# Thermostat_EEM_Cryo.net
KiCad netlist of a schematic drawn in Altium Designer
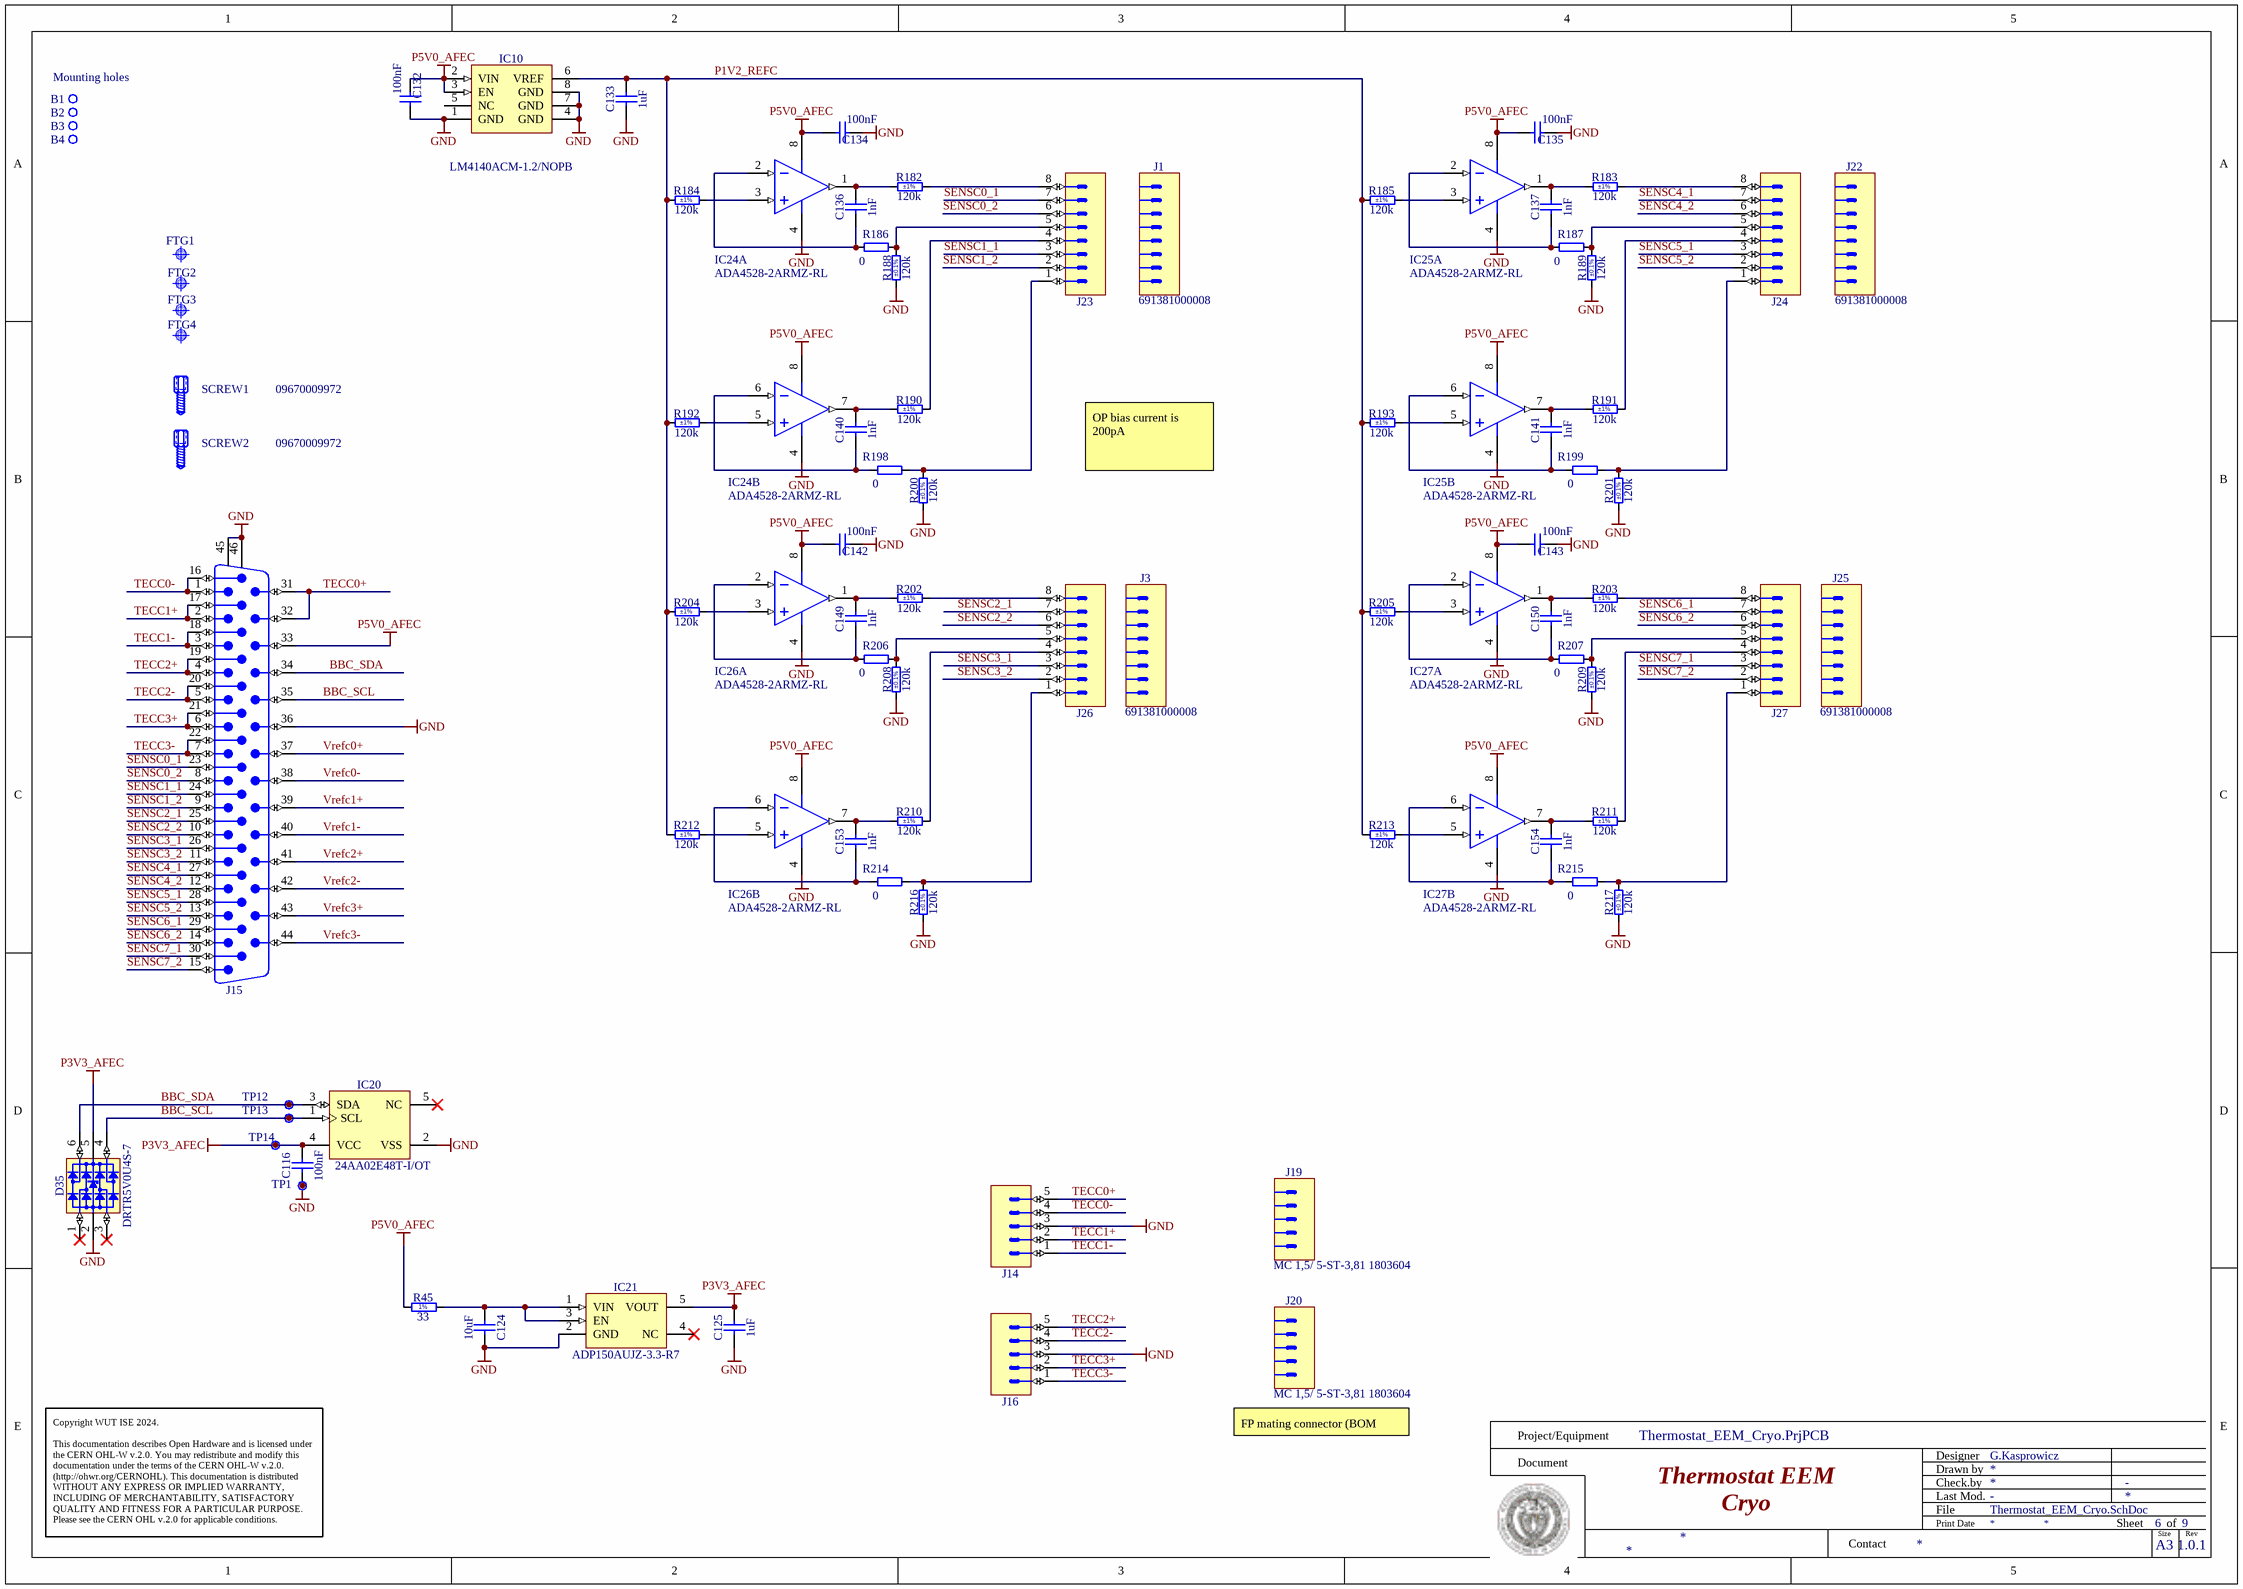
[diagram p0: Thermostat_EEM_Cryo.SchDoc]

(export (version "E")
  (design (tool "Eeschema 10.0.6"))
  (components
    (comp (ref "B1")
      (value "Plated Hole")
      (footprint "MTG320_550")
      (description "Single Terminal Socket")
      (fields (field (name "PART NUMBER") "PLATED_HOLE3.2_PAD5.5") (field (name "AUTHOR") "CERN DEM JMW"))
      (libsource (lib "Eletro-mechanical") (part "Single Terminal Socket"))
    )
    (comp (ref "B2")
      (value "Plated Hole")
      (footprint "MTG320_550")
      (description "Single Terminal Socket")
      (fields (field (name "PART NUMBER") "PLATED_HOLE3.2_PAD5.5") (field (name "AUTHOR") "CERN DEM JMW"))
      (libsource (lib "Eletro-mechanical") (part "Single Terminal Socket"))
    )
    (comp (ref "B3")
      (value "Plated Hole")
      (footprint "MTG320_550")
      (description "Single Terminal Socket")
      (fields (field (name "PART NUMBER") "PLATED_HOLE3.2_PAD5.5") (field (name "AUTHOR") "CERN DEM JMW"))
      (libsource (lib "Eletro-mechanical") (part "Single Terminal Socket"))
    )
    (comp (ref "B4")
      (value "Plated Hole")
      (footprint "MTG320_550")
      (description "Single Terminal Socket")
      (fields (field (name "PART NUMBER") "PLATED_HOLE3.2_PAD5.5") (field (name "AUTHOR") "CERN DEM JMW"))
      (libsource (lib "Eletro-mechanical") (part "Single Terminal Socket"))
    )
    (comp (ref "C116")
      (value "100nF")
      (footprint "CAPC1005X55N")
      (description "Non-polarised capacitor")
      (fields
        (field (name "PART NUMBER") "CC0402_100NF_16V_10%_X5R")
        (field (name "VOLTAGE") "16V")
        (field (name "AUTHOR") "CERN DEM JLC")
      )
      (libsource (lib "Capacitors") (part "Capacitor - non polarized"))
    )
    (comp (ref "C124")
      (value "10uF")
      (footprint "CAPC2012X135N")
      (description "Non-polarised capacitor")
      (fields
        (field (name "PART NUMBER") "CC0805_10UF_16V_10%_X5R")
        (field (name "VOLTAGE") "16V")
        (field (name "AUTHOR") "CERN DEM JLC")
      )
      (libsource (lib "Capacitors") (part "Capacitor - non polarized"))
    )
    (comp (ref "C125")
      (value "1uF")
      (footprint "CAPC1608X87N")
      (description "Non-polarised capacitor")
      (fields
        (field (name "PART NUMBER") "CC0603_1UF_25V_10%_X7R")
        (field (name "VOLTAGE") "25V")
        (field (name "AUTHOR") "CERN DEM JLC")
      )
      (libsource (lib "Capacitors") (part "Capacitor - non polarized"))
    )
    (comp (ref "C132")
      (value "100nF")
      (footprint "CAPC1005X55N")
      (description "Non-polarised capacitor")
      (fields
        (field (name "PART NUMBER") "CC0402_100NF_16V_10%_X5R")
        (field (name "VOLTAGE") "16V")
        (field (name "AUTHOR") "CERN DEM JLC")
      )
      (libsource (lib "Capacitors") (part "Capacitor - non polarized"))
    )
    (comp (ref "C133")
      (value "1uF")
      (footprint "CAPC1608X87N")
      (description "Non-polarised capacitor")
      (fields
        (field (name "PART NUMBER") "CC0603_1UF_25V_10%_X7R")
        (field (name "VOLTAGE") "25V")
        (field (name "AUTHOR") "CERN DEM JLC")
      )
      (libsource (lib "Capacitors") (part "Capacitor - non polarized"))
    )
    (comp (ref "C134")
      (value "100nF")
      (footprint "CAPC1005X55N")
      (description "Non-polarised capacitor")
      (fields
        (field (name "PART NUMBER") "CC0402_100NF_16V_10%_X5R")
        (field (name "VOLTAGE") "16V")
        (field (name "AUTHOR") "CERN DEM JLC")
      )
      (libsource (lib "Capacitors") (part "Capacitor - non polarized"))
    )
    (comp (ref "C135")
      (value "100nF")
      (footprint "CAPC1005X55N")
      (description "Non-polarised capacitor")
      (fields
        (field (name "PART NUMBER") "CC0402_100NF_16V_10%_X5R")
        (field (name "VOLTAGE") "16V")
        (field (name "AUTHOR") "CERN DEM JLC")
      )
      (libsource (lib "Capacitors") (part "Capacitor - non polarized"))
    )
    (comp (ref "C136")
      (value "1nF")
      (footprint "CAPC1005X55N")
      (description "Non-polarised capacitor")
      (fields
        (field (name "PART NUMBER") "CC0402_1NF_50V_10%_X7R")
        (field (name "VOLTAGE") "50V")
        (field (name "AUTHOR") "CERN DEM JLC")
      )
      (libsource (lib "Capacitors") (part "Capacitor - non polarized"))
    )
    (comp (ref "C137")
      (value "1nF")
      (footprint "CAPC1005X55N")
      (description "Non-polarised capacitor")
      (fields
        (field (name "PART NUMBER") "CC0402_1NF_50V_10%_X7R")
        (field (name "VOLTAGE") "50V")
        (field (name "AUTHOR") "CERN DEM JLC")
      )
      (libsource (lib "Capacitors") (part "Capacitor - non polarized"))
    )
    (comp (ref "C140")
      (value "1nF")
      (footprint "CAPC1005X55N")
      (description "Non-polarised capacitor")
      (fields
        (field (name "PART NUMBER") "CC0402_1NF_50V_10%_X7R")
        (field (name "VOLTAGE") "50V")
        (field (name "AUTHOR") "CERN DEM JLC")
      )
      (libsource (lib "Capacitors") (part "Capacitor - non polarized"))
    )
    (comp (ref "C141")
      (value "1nF")
      (footprint "CAPC1005X55N")
      (description "Non-polarised capacitor")
      (fields
        (field (name "PART NUMBER") "CC0402_1NF_50V_10%_X7R")
        (field (name "VOLTAGE") "50V")
        (field (name "AUTHOR") "CERN DEM JLC")
      )
      (libsource (lib "Capacitors") (part "Capacitor - non polarized"))
    )
    (comp (ref "C142")
      (value "100nF")
      (footprint "CAPC1005X55N")
      (description "Non-polarised capacitor")
      (fields
        (field (name "PART NUMBER") "CC0402_100NF_16V_10%_X5R")
        (field (name "VOLTAGE") "16V")
        (field (name "AUTHOR") "CERN DEM JLC")
      )
      (libsource (lib "Capacitors") (part "Capacitor - non polarized"))
    )
    (comp (ref "C143")
      (value "100nF")
      (footprint "CAPC1005X55N")
      (description "Non-polarised capacitor")
      (fields
        (field (name "PART NUMBER") "CC0402_100NF_16V_10%_X5R")
        (field (name "VOLTAGE") "16V")
        (field (name "AUTHOR") "CERN DEM JLC")
      )
      (libsource (lib "Capacitors") (part "Capacitor - non polarized"))
    )
    (comp (ref "C149")
      (value "1nF")
      (footprint "CAPC1005X55N")
      (description "Non-polarised capacitor")
      (fields
        (field (name "PART NUMBER") "CC0402_1NF_50V_10%_X7R")
        (field (name "VOLTAGE") "50V")
        (field (name "AUTHOR") "CERN DEM JLC")
      )
      (libsource (lib "Capacitors") (part "Capacitor - non polarized"))
    )
    (comp (ref "C150")
      (value "1nF")
      (footprint "CAPC1005X55N")
      (description "Non-polarised capacitor")
      (fields
        (field (name "PART NUMBER") "CC0402_1NF_50V_10%_X7R")
        (field (name "VOLTAGE") "50V")
        (field (name "AUTHOR") "CERN DEM JLC")
      )
      (libsource (lib "Capacitors") (part "Capacitor - non polarized"))
    )
    (comp (ref "C153")
      (value "1nF")
      (footprint "CAPC1005X55N")
      (description "Non-polarised capacitor")
      (fields
        (field (name "PART NUMBER") "CC0402_1NF_50V_10%_X7R")
        (field (name "VOLTAGE") "50V")
        (field (name "AUTHOR") "CERN DEM JLC")
      )
      (libsource (lib "Capacitors") (part "Capacitor - non polarized"))
    )
    (comp (ref "C154")
      (value "1nF")
      (footprint "CAPC1005X55N")
      (description "Non-polarised capacitor")
      (fields
        (field (name "PART NUMBER") "CC0402_1NF_50V_10%_X7R")
        (field (name "VOLTAGE") "50V")
        (field (name "AUTHOR") "CERN DEM JLC")
      )
      (libsource (lib "Capacitors") (part "Capacitor - non polarized"))
    )
    (comp (ref "D35")
      (value "DRTR5V0U4S-7")
      (footprint "SOT65P210X110-6N")
      (description "Integrated Quad Ultra-Low Capacitance ESD Protection")
      (fields (field (name "MANUFACTURER") "DIODES") (field (name "AUTHOR") "GK"))
      (libsource (lib "Diodes") (part "D_TVS_DRTR5V0U4S-7"))
    )
    (comp (ref "FTG1")
      (value "Use only in PCB")
      (footprint "FIDUCIAL_TOP_S100-200")
      (description "Fiducial Target")
      (fields (field (name "PART NUMBER") "FIDUCIAL_TARGET_S100-200") (field (name "AUTHOR") "CERN DEM JLC"))
      (libsource (lib "Eletro-mechanical") (part "Fiducial Target"))
    )
    (comp (ref "FTG2")
      (value "Use only in PCB")
      (footprint "FIDUCIAL_TOP_S100-200")
      (description "Fiducial Target")
      (fields (field (name "PART NUMBER") "FIDUCIAL_TARGET_S100-200") (field (name "AUTHOR") "CERN DEM JLC"))
      (libsource (lib "Eletro-mechanical") (part "Fiducial Target"))
    )
    (comp (ref "FTG3")
      (value "Use only in PCB")
      (footprint "FIDUCIAL_TOP_S100-200")
      (description "Fiducial Target")
      (fields (field (name "PART NUMBER") "FIDUCIAL_TARGET_S100-200") (field (name "AUTHOR") "CERN DEM JLC"))
      (libsource (lib "Eletro-mechanical") (part "Fiducial Target"))
    )
    (comp (ref "FTG4")
      (value "Use only in PCB")
      (footprint "FIDUCIAL_TOP_S100-200")
      (description "Fiducial Target")
      (fields (field (name "PART NUMBER") "FIDUCIAL_TARGET_S100-200") (field (name "AUTHOR") "CERN DEM JLC"))
      (libsource (lib "Eletro-mechanical") (part "Fiducial Target"))
    )
    (comp (ref "IC10")
      (value "LM4140ACM-1.2/NOPB")
      (footprint "SOIC127P600X175-8N")
      (description "High Precision Low Noise Low Dropout Voltage Reference")
      (fields (field (name "MANUFACTURER") "TEXAS INSTRUMENTS") (field (name "AUTHOR") "CERN DEM JLC"))
      (libsource (lib "ICs And Semiconductors") (part "LM4140"))
    )
    (comp (ref "IC20")
      (value "24AA02E48T-I/OT")
      (footprint "SOT95P280X145-5N")
      (description "1.7V-5.5V, 2K I2C Serial EEPROM With EUI-48 Node Identity")
      (fields (field (name "MANUFACTURER") "MICROCHIP TECHNOLOGY") (field (name "AUTHOR") "CERN DEM MR"))
      (libsource (lib "ICs And Semiconductors") (part "24AA02E48T-I/OT"))
    )
    (comp (ref "IC21")
      (value "ADP150AUJZ-3.3-R7")
      (footprint "SOT95P280X90-5N")
      (description "Ultralow Noise, 150 mA CMOS Linear Regulator")
      (fields (field (name "MANUFACTURER") "ANALOG DEVICES") (field (name "AUTHOR") "CERN DEM JLC"))
      (libsource (lib "ICs And Semiconductors") (part "ADP150AUJZ"))
    )
    (comp (ref "IC24")
      (value "ADA4528-2ARMZ-RL")
      (footprint "ADI-RM-8_N")
      (fields (field (name "GENERIC PART NUMBER") "ADA4528-2") (field (name "MANUFACTURER") "Analog Devices"))
      (libsource (lib "Altium Content Vault") (part "ADI-ADA4000-2-X-8"))
    )
    (comp (ref "IC25")
      (value "ADA4528-2ARMZ-RL")
      (footprint "ADI-RM-8_N")
      (fields (field (name "GENERIC PART NUMBER") "ADA4528-2") (field (name "MANUFACTURER") "Analog Devices"))
      (libsource (lib "Altium Content Vault") (part "ADI-ADA4000-2-X-8"))
    )
    (comp (ref "IC26")
      (value "ADA4528-2ARMZ-RL")
      (footprint "ADI-RM-8_N")
      (fields (field (name "GENERIC PART NUMBER") "ADA4528-2") (field (name "MANUFACTURER") "Analog Devices"))
      (libsource (lib "Altium Content Vault") (part "ADI-ADA4000-2-X-8"))
    )
    (comp (ref "IC27")
      (value "ADA4528-2ARMZ-RL")
      (footprint "ADI-RM-8_N")
      (fields (field (name "GENERIC PART NUMBER") "ADA4528-2") (field (name "MANUFACTURER") "Analog Devices"))
      (libsource (lib "Altium Content Vault") (part "ADI-ADA4000-2-X-8"))
    )
    (comp (ref "J1")
      (value "691381000008")
      (footprint "WURTH_691381000008")
      (description "Phoenix Contact 2.5 pitch terminal plug, 8 ways")
      (fields (field (name "MANUFACTURER") "WURTH") (field (name "MANUFACTURER PART NUMBER") "691381000008"))
      (libsource (lib "Connectors") (part "CON_TB_WURTH_691381000008"))
    )
    (comp (ref "J3")
      (value "691381000008")
      (footprint "WURTH_691381000008")
      (description "Phoenix Contact 2.5 pitch terminal plug, 8 ways")
      (fields (field (name "MANUFACTURER") "WURTH") (field (name "MANUFACTURER PART NUMBER") "691381000008"))
      (libsource (lib "Connectors") (part "CON_TB_WURTH_691381000008"))
    )
    (comp (ref "J14")
      (value "~")
      (footprint "PHOENIX_1803455")
      (description "Connector 5 Male")
      (fields
        (field (name "PART NUMBER") "PHOENIX_1803455")
        (field (name "MANUFACTURER") "PHOENIX CONTACT")
        (field (name "AUTHOR") "CERN DEM JLC")
      )
      (libsource (lib "Connectors") (part "Connector 5 Male"))
    )
    (comp (ref "J15")
      (value "D-Sub")
      (footprint "AMPHENOL_10090926-P444XLF")
      (description "Connector D-sub 44 Male")
      (fields
        (field (name "PART NUMBER") "AMPHENOL_10090926-P444XLF")
        (field (name "MANUFACTURER") "AMPHENOL")
        (field (name "AUTHOR") "CERN DEM BC")
      )
      (libsource (lib "Connectors") (part "Connector D-sub 44 Male"))
    )
    (comp (ref "J16")
      (value "~")
      (footprint "PHOENIX_1803455")
      (description "Connector 5 Male")
      (fields
        (field (name "PART NUMBER") "PHOENIX_1803455")
        (field (name "MANUFACTURER") "PHOENIX CONTACT")
        (field (name "AUTHOR") "CERN DEM JLC")
      )
      (libsource (lib "Connectors") (part "Connector 5 Male"))
    )
    (comp (ref "J19")
      (value "~")
      (footprint "PHOENIX_1803604")
      (description "Phoenix Contact 3.81 pitch terminal plug, 5 ways")
      (fields
        (field (name "MANUFACTURER") "Phoenix Contact")
        (field (name "MANUFACTURER PART NUMBER") "MC 1,5/ 5-ST-3,81 1803604")
      )
      (libsource (lib "Connectors") (part "PHOENIX_1803604"))
    )
    (comp (ref "J20")
      (value "~")
      (footprint "PHOENIX_1803604")
      (description "Phoenix Contact 3.81 pitch terminal plug, 5 ways")
      (fields
        (field (name "MANUFACTURER") "Phoenix Contact")
        (field (name "MANUFACTURER PART NUMBER") "MC 1,5/ 5-ST-3,81 1803604")
      )
      (libsource (lib "Connectors") (part "PHOENIX_1803604"))
    )
    (comp (ref "J22")
      (value "691381000008")
      (footprint "WURTH_691381000008")
      (description "Phoenix Contact 2.5 pitch terminal plug, 8 ways")
      (fields (field (name "MANUFACTURER") "WURTH") (field (name "MANUFACTURER PART NUMBER") "691381000008"))
      (libsource (lib "Connectors") (part "CON_TB_WURTH_691381000008"))
    )
    (comp (ref "J23")
      (value "~")
      (footprint "PHOENIX_1881613")
      (description "Connector 8 Male")
      (fields
        (field (name "PART NUMBER") "PHOENIX_1881613")
        (field (name "MANUFACTURER") "PHOENIX CONTACT")
        (field (name "AUTHOR") "CERN DEM JLC")
      )
      (libsource (lib "Connectors") (part "Connector 8 Male"))
    )
    (comp (ref "J24")
      (value "~")
      (footprint "PHOENIX_1881613")
      (description "Connector 8 Male")
      (fields
        (field (name "PART NUMBER") "PHOENIX_1881613")
        (field (name "MANUFACTURER") "PHOENIX CONTACT")
        (field (name "AUTHOR") "CERN DEM JLC")
      )
      (libsource (lib "Connectors") (part "Connector 8 Male"))
    )
    (comp (ref "J25")
      (value "691381000008")
      (footprint "WURTH_691381000008")
      (description "Phoenix Contact 2.5 pitch terminal plug, 8 ways")
      (fields (field (name "MANUFACTURER") "WURTH") (field (name "MANUFACTURER PART NUMBER") "691381000008"))
      (libsource (lib "Connectors") (part "CON_TB_WURTH_691381000008"))
    )
    (comp (ref "J26")
      (value "~")
      (footprint "PHOENIX_1881613")
      (description "Connector 8 Male")
      (fields
        (field (name "PART NUMBER") "PHOENIX_1881613")
        (field (name "MANUFACTURER") "PHOENIX CONTACT")
        (field (name "AUTHOR") "CERN DEM JLC")
      )
      (libsource (lib "Connectors") (part "Connector 8 Male"))
    )
    (comp (ref "J27")
      (value "~")
      (footprint "PHOENIX_1881613")
      (description "Connector 8 Male")
      (fields
        (field (name "PART NUMBER") "PHOENIX_1881613")
        (field (name "MANUFACTURER") "PHOENIX CONTACT")
        (field (name "AUTHOR") "CERN DEM JLC")
      )
      (libsource (lib "Connectors") (part "Connector 8 Male"))
    )
    (comp (ref "R45")
      (value "33")
      (footprint "RESC1005X40N")
      (description "Resistor - 1%")
      (fields
        (field (name "PART NUMBER") "R0402_33R_1%_0.0625W_100PPM")
        (field (name "POWER") "0.0625W")
        (field (name "AUTHOR") "CERN DEM JLC")
      )
      (libsource (lib "Resistors") (part "Resistor - 1%"))
    )
    (comp (ref "R182")
      (value "120k")
      (footprint "RESC1005X40N")
      (description "Resistor - 1%")
      (fields
        (field (name "TOLERANCE") "±1%")
        (field (name "PART NUMBER") "R0402_120K_1%_0.0625W_100PPM")
        (field (name "POWER") "0.0625W")
        (field (name "AUTHOR") "CERN DEM JLC")
      )
      (libsource (lib "Resistors") (part "Resistor - 1%"))
    )
    (comp (ref "R183")
      (value "120k")
      (footprint "RESC1005X40N")
      (description "Resistor - 1%")
      (fields
        (field (name "TOLERANCE") "±1%")
        (field (name "PART NUMBER") "R0402_120K_1%_0.0625W_100PPM")
        (field (name "POWER") "0.0625W")
        (field (name "AUTHOR") "CERN DEM JLC")
      )
      (libsource (lib "Resistors") (part "Resistor - 1%"))
    )
    (comp (ref "R184")
      (value "120k")
      (footprint "RESC1005X40N")
      (description "Resistor - 1%")
      (fields
        (field (name "TOLERANCE") "±1%")
        (field (name "PART NUMBER") "R0402_120K_1%_0.0625W_100PPM")
        (field (name "POWER") "0.0625W")
        (field (name "AUTHOR") "CERN DEM JLC")
      )
      (libsource (lib "Resistors") (part "Resistor - 1%"))
    )
    (comp (ref "R185")
      (value "120k")
      (footprint "RESC1005X40N")
      (description "Resistor - 1%")
      (fields
        (field (name "TOLERANCE") "±1%")
        (field (name "PART NUMBER") "R0402_120K_1%_0.0625W_100PPM")
        (field (name "POWER") "0.0625W")
        (field (name "AUTHOR") "CERN DEM JLC")
      )
      (libsource (lib "Resistors") (part "Resistor - 1%"))
    )
    (comp (ref "R186")
      (value "0")
      (footprint "RESC1608X55N")
      (description "Resistor")
      (fields
        (field (name "PART NUMBER") "R0603_0R_JUMPER")
        (field (name "MANUFACTURER") "GENERIC")
        (field (name "AUTHOR") "CERN DEM JLC")
      )
      (libsource (lib "Resistors") (part "Resistor"))
    )
    (comp (ref "R187")
      (value "0")
      (footprint "RESC1608X55N")
      (description "Resistor")
      (fields
        (field (name "PART NUMBER") "R0603_0R_JUMPER")
        (field (name "MANUFACTURER") "GENERIC")
        (field (name "AUTHOR") "CERN DEM JLC")
      )
      (libsource (lib "Resistors") (part "Resistor"))
    )
    (comp (ref "R188")
      (value "120k")
      (footprint "RESC2012X60N")
      (description "Resistor - 0.1%")
      (fields
        (field (name "TOLERANCE") "±0.1%")
        (field (name "PART NUMBER") "R0805_120K_0.1%_0.125W_25PPM")
        (field (name "POWER") "0.125W")
        (field (name "AUTHOR") "CERN DEM JLC")
      )
      (libsource (lib "Resistors") (part "Resistor - 0.1%"))
    )
    (comp (ref "R189")
      (value "120k")
      (footprint "RESC2012X60N")
      (description "Resistor - 0.1%")
      (fields
        (field (name "TOLERANCE") "±0.1%")
        (field (name "PART NUMBER") "R0805_120K_0.1%_0.125W_25PPM")
        (field (name "POWER") "0.125W")
        (field (name "AUTHOR") "CERN DEM JLC")
      )
      (libsource (lib "Resistors") (part "Resistor - 0.1%"))
    )
    (comp (ref "R190")
      (value "120k")
      (footprint "RESC1005X40N")
      (description "Resistor - 1%")
      (fields
        (field (name "TOLERANCE") "±1%")
        (field (name "PART NUMBER") "R0402_120K_1%_0.0625W_100PPM")
        (field (name "POWER") "0.0625W")
        (field (name "AUTHOR") "CERN DEM JLC")
      )
      (libsource (lib "Resistors") (part "Resistor - 1%"))
    )
    (comp (ref "R191")
      (value "120k")
      (footprint "RESC1005X40N")
      (description "Resistor - 1%")
      (fields
        (field (name "TOLERANCE") "±1%")
        (field (name "PART NUMBER") "R0402_120K_1%_0.0625W_100PPM")
        (field (name "POWER") "0.0625W")
        (field (name "AUTHOR") "CERN DEM JLC")
      )
      (libsource (lib "Resistors") (part "Resistor - 1%"))
    )
    (comp (ref "R192")
      (value "120k")
      (footprint "RESC1005X40N")
      (description "Resistor - 1%")
      (fields
        (field (name "TOLERANCE") "±1%")
        (field (name "PART NUMBER") "R0402_120K_1%_0.0625W_100PPM")
        (field (name "POWER") "0.0625W")
        (field (name "AUTHOR") "CERN DEM JLC")
      )
      (libsource (lib "Resistors") (part "Resistor - 1%"))
    )
    (comp (ref "R193")
      (value "120k")
      (footprint "RESC1005X40N")
      (description "Resistor - 1%")
      (fields
        (field (name "TOLERANCE") "±1%")
        (field (name "PART NUMBER") "R0402_120K_1%_0.0625W_100PPM")
        (field (name "POWER") "0.0625W")
        (field (name "AUTHOR") "CERN DEM JLC")
      )
      (libsource (lib "Resistors") (part "Resistor - 1%"))
    )
    (comp (ref "R198")
      (value "0")
      (footprint "RESC1608X55N")
      (description "Resistor")
      (fields
        (field (name "PART NUMBER") "R0603_0R_JUMPER")
        (field (name "MANUFACTURER") "GENERIC")
        (field (name "AUTHOR") "CERN DEM JLC")
      )
      (libsource (lib "Resistors") (part "Resistor"))
    )
    (comp (ref "R199")
      (value "0")
      (footprint "RESC1608X55N")
      (description "Resistor")
      (fields
        (field (name "PART NUMBER") "R0603_0R_JUMPER")
        (field (name "MANUFACTURER") "GENERIC")
        (field (name "AUTHOR") "CERN DEM JLC")
      )
      (libsource (lib "Resistors") (part "Resistor"))
    )
    (comp (ref "R200")
      (value "120k")
      (footprint "RESC2012X60N")
      (description "Resistor - 0.1%")
      (fields
        (field (name "TOLERANCE") "±0.1%")
        (field (name "PART NUMBER") "R0805_120K_0.1%_0.125W_25PPM")
        (field (name "POWER") "0.125W")
        (field (name "AUTHOR") "CERN DEM JLC")
      )
      (libsource (lib "Resistors") (part "Resistor - 0.1%"))
    )
    (comp (ref "R201")
      (value "120k")
      (footprint "RESC2012X60N")
      (description "Resistor - 0.1%")
      (fields
        (field (name "TOLERANCE") "±0.1%")
        (field (name "PART NUMBER") "R0805_120K_0.1%_0.125W_25PPM")
        (field (name "POWER") "0.125W")
        (field (name "AUTHOR") "CERN DEM JLC")
      )
      (libsource (lib "Resistors") (part "Resistor - 0.1%"))
    )
    (comp (ref "R202")
      (value "120k")
      (footprint "RESC1005X40N")
      (description "Resistor - 1%")
      (fields
        (field (name "TOLERANCE") "±1%")
        (field (name "PART NUMBER") "R0402_120K_1%_0.0625W_100PPM")
        (field (name "POWER") "0.0625W")
        (field (name "AUTHOR") "CERN DEM JLC")
      )
      (libsource (lib "Resistors") (part "Resistor - 1%"))
    )
    (comp (ref "R203")
      (value "120k")
      (footprint "RESC1005X40N")
      (description "Resistor - 1%")
      (fields
        (field (name "TOLERANCE") "±1%")
        (field (name "PART NUMBER") "R0402_120K_1%_0.0625W_100PPM")
        (field (name "POWER") "0.0625W")
        (field (name "AUTHOR") "CERN DEM JLC")
      )
      (libsource (lib "Resistors") (part "Resistor - 1%"))
    )
    (comp (ref "R204")
      (value "120k")
      (footprint "RESC1005X40N")
      (description "Resistor - 1%")
      (fields
        (field (name "TOLERANCE") "±1%")
        (field (name "PART NUMBER") "R0402_120K_1%_0.0625W_100PPM")
        (field (name "POWER") "0.0625W")
        (field (name "AUTHOR") "CERN DEM JLC")
      )
      (libsource (lib "Resistors") (part "Resistor - 1%"))
    )
    (comp (ref "R205")
      (value "120k")
      (footprint "RESC1005X40N")
      (description "Resistor - 1%")
      (fields
        (field (name "TOLERANCE") "±1%")
        (field (name "PART NUMBER") "R0402_120K_1%_0.0625W_100PPM")
        (field (name "POWER") "0.0625W")
        (field (name "AUTHOR") "CERN DEM JLC")
      )
      (libsource (lib "Resistors") (part "Resistor - 1%"))
    )
    (comp (ref "R206")
      (value "0")
      (footprint "RESC1608X55N")
      (description "Resistor")
      (fields
        (field (name "PART NUMBER") "R0603_0R_JUMPER")
        (field (name "MANUFACTURER") "GENERIC")
        (field (name "AUTHOR") "CERN DEM JLC")
      )
      (libsource (lib "Resistors") (part "Resistor"))
    )
    (comp (ref "R207")
      (value "0")
      (footprint "RESC1608X55N")
      (description "Resistor")
      (fields
        (field (name "PART NUMBER") "R0603_0R_JUMPER")
        (field (name "MANUFACTURER") "GENERIC")
        (field (name "AUTHOR") "CERN DEM JLC")
      )
      (libsource (lib "Resistors") (part "Resistor"))
    )
    (comp (ref "R208")
      (value "120k")
      (footprint "RESC2012X60N")
      (description "Resistor - 0.1%")
      (fields
        (field (name "TOLERANCE") "±0.1%")
        (field (name "PART NUMBER") "R0805_120K_0.1%_0.125W_25PPM")
        (field (name "POWER") "0.125W")
        (field (name "AUTHOR") "CERN DEM JLC")
      )
      (libsource (lib "Resistors") (part "Resistor - 0.1%"))
    )
    (comp (ref "R209")
      (value "120k")
      (footprint "RESC2012X60N")
      (description "Resistor - 0.1%")
      (fields
        (field (name "TOLERANCE") "±0.1%")
        (field (name "PART NUMBER") "R0805_120K_0.1%_0.125W_25PPM")
        (field (name "POWER") "0.125W")
        (field (name "AUTHOR") "CERN DEM JLC")
      )
      (libsource (lib "Resistors") (part "Resistor - 0.1%"))
    )
    (comp (ref "R210")
      (value "120k")
      (footprint "RESC1005X40N")
      (description "Resistor - 1%")
      (fields
        (field (name "TOLERANCE") "±1%")
        (field (name "PART NUMBER") "R0402_120K_1%_0.0625W_100PPM")
        (field (name "POWER") "0.0625W")
        (field (name "AUTHOR") "CERN DEM JLC")
      )
      (libsource (lib "Resistors") (part "Resistor - 1%"))
    )
    (comp (ref "R211")
      (value "120k")
      (footprint "RESC1005X40N")
      (description "Resistor - 1%")
      (fields
        (field (name "TOLERANCE") "±1%")
        (field (name "PART NUMBER") "R0402_120K_1%_0.0625W_100PPM")
        (field (name "POWER") "0.0625W")
        (field (name "AUTHOR") "CERN DEM JLC")
      )
      (libsource (lib "Resistors") (part "Resistor - 1%"))
    )
    (comp (ref "R212")
      (value "120k")
      (footprint "RESC1005X40N")
      (description "Resistor - 1%")
      (fields
        (field (name "TOLERANCE") "±1%")
        (field (name "PART NUMBER") "R0402_120K_1%_0.0625W_100PPM")
        (field (name "POWER") "0.0625W")
        (field (name "AUTHOR") "CERN DEM JLC")
      )
      (libsource (lib "Resistors") (part "Resistor - 1%"))
    )
    (comp (ref "R213")
      (value "120k")
      (footprint "RESC1005X40N")
      (description "Resistor - 1%")
      (fields
        (field (name "TOLERANCE") "±1%")
        (field (name "PART NUMBER") "R0402_120K_1%_0.0625W_100PPM")
        (field (name "POWER") "0.0625W")
        (field (name "AUTHOR") "CERN DEM JLC")
      )
      (libsource (lib "Resistors") (part "Resistor - 1%"))
    )
    (comp (ref "R214")
      (value "0")
      (footprint "RESC1608X55N")
      (description "Resistor")
      (fields
        (field (name "PART NUMBER") "R0603_0R_JUMPER")
        (field (name "MANUFACTURER") "GENERIC")
        (field (name "AUTHOR") "CERN DEM JLC")
      )
      (libsource (lib "Resistors") (part "Resistor"))
    )
    (comp (ref "R215")
      (value "0")
      (footprint "RESC1608X55N")
      (description "Resistor")
      (fields
        (field (name "PART NUMBER") "R0603_0R_JUMPER")
        (field (name "MANUFACTURER") "GENERIC")
        (field (name "AUTHOR") "CERN DEM JLC")
      )
      (libsource (lib "Resistors") (part "Resistor"))
    )
    (comp (ref "R216")
      (value "120k")
      (footprint "RESC2012X60N")
      (description "Resistor - 0.1%")
      (fields
        (field (name "TOLERANCE") "±0.1%")
        (field (name "PART NUMBER") "R0805_120K_0.1%_0.125W_25PPM")
        (field (name "POWER") "0.125W")
        (field (name "AUTHOR") "CERN DEM JLC")
      )
      (libsource (lib "Resistors") (part "Resistor - 0.1%"))
    )
    (comp (ref "R217")
      (value "120k")
      (footprint "RESC2012X60N")
      (description "Resistor - 0.1%")
      (fields
        (field (name "TOLERANCE") "±0.1%")
        (field (name "PART NUMBER") "R0805_120K_0.1%_0.125W_25PPM")
        (field (name "POWER") "0.125W")
        (field (name "AUTHOR") "CERN DEM JLC")
      )
      (libsource (lib "Resistors") (part "Resistor - 0.1%"))
    )
    (comp (ref "SCREW1")
      (value "09670009972")
      (footprint "3M_3341-31")
      (description "Female Screw Lock")
      (fields (field (name "MANUFACTURER") "HARTING") (field (name "AUTHOR") "GK"))
      (libsource (lib "Mechanical") (part "MECH_MDR_screw_lock"))
    )
    (comp (ref "SCREW2")
      (value "09670009972")
      (footprint "3M_3341-31")
      (description "Female Screw Lock")
      (fields (field (name "MANUFACTURER") "HARTING") (field (name "AUTHOR") "GK"))
      (libsource (lib "Mechanical") (part "MECH_MDR_screw_lock"))
    )
    (comp (ref "TP1")
      (value "Test Point")
      (footprint "TPS127")
      (fields (field (name "PART NUMBER") "SMD_PAD_1.27X1.27MM") (field (name "AUTHOR") "CERN DEM JLC"))
      (libsource (lib "Eletro-mechanical") (part "Test Point"))
    )
    (comp (ref "TP12")
      (value "Test Point")
      (footprint "TPS127")
      (fields (field (name "PART NUMBER") "SMD_PAD_1.27X1.27MM") (field (name "AUTHOR") "CERN DEM JLC"))
      (libsource (lib "Eletro-mechanical") (part "Test Point"))
    )
    (comp (ref "TP13")
      (value "Test Point")
      (footprint "TPS127")
      (fields (field (name "PART NUMBER") "SMD_PAD_1.27X1.27MM") (field (name "AUTHOR") "CERN DEM JLC"))
      (libsource (lib "Eletro-mechanical") (part "Test Point"))
    )
    (comp (ref "TP14")
      (value "Test Point")
      (footprint "TPS127")
      (fields (field (name "PART NUMBER") "SMD_PAD_1.27X1.27MM") (field (name "AUTHOR") "CERN DEM JLC"))
      (libsource (lib "Eletro-mechanical") (part "Test Point"))
    )
  )
  (nets
    (net (code "1") (name "/BBC_SCL") (class "Default")
      (node (ref "D35") (pin "4") (pinfunction "I/O3_4") (pintype "bidirectional"))
      (node (ref "IC20") (pin "1") (pinfunction "SCL_1") (pintype "input"))
      (node (ref "J15") (pin "35") (pinfunction "35_35") (pintype "bidirectional"))
      (node (ref "TP13") (pin "1") (pinfunction "1_1") (pintype "bidirectional"))
    )
    (net (code "2") (name "/BBC_SDA") (class "Default")
      (node (ref "D35") (pin "6") (pinfunction "I/O4_6") (pintype "bidirectional"))
      (node (ref "IC20") (pin "3") (pinfunction "SDA_3") (pintype "bidirectional"))
      (node (ref "J15") (pin "34") (pinfunction "34_34") (pintype "bidirectional"))
      (node (ref "TP12") (pin "1") (pinfunction "1_1") (pintype "bidirectional"))
    )
    (net (code "3") (name "/P1V2_REFC") (class "Default")
      (node (ref "C133") (pin "2") (pinfunction "2_2") (pintype "passive"))
      (node (ref "IC10") (pin "6") (pinfunction "VREF_6") (pintype "power_in"))
      (node (ref "R184") (pin "1") (pinfunction "1_1") (pintype "passive"))
      (node (ref "R185") (pin "1") (pinfunction "1_1") (pintype "passive"))
      (node (ref "R192") (pin "1") (pinfunction "1_1") (pintype "passive"))
      (node (ref "R193") (pin "1") (pinfunction "1_1") (pintype "passive"))
      (node (ref "R204") (pin "1") (pinfunction "1_1") (pintype "passive"))
      (node (ref "R205") (pin "1") (pinfunction "1_1") (pintype "passive"))
      (node (ref "R212") (pin "1") (pinfunction "1_1") (pintype "passive"))
      (node (ref "R213") (pin "1") (pinfunction "1_1") (pintype "passive"))
    )
    (net (code "4") (name "/SENSC0_1") (class "Default")
      (node (ref "J15") (pin "23") (pinfunction "23_23") (pintype "bidirectional"))
      (node (ref "J23") (pin "7") (pinfunction "7_7") (pintype "bidirectional"))
    )
    (net (code "5") (name "/SENSC0_2") (class "Default")
      (node (ref "J15") (pin "8") (pinfunction "8_8") (pintype "bidirectional"))
      (node (ref "J23") (pin "6") (pinfunction "6_6") (pintype "bidirectional"))
    )
    (net (code "6") (name "/SENSC1_1") (class "Default")
      (node (ref "J15") (pin "24") (pinfunction "24_24") (pintype "bidirectional"))
      (node (ref "J23") (pin "3") (pinfunction "3_3") (pintype "bidirectional"))
    )
    (net (code "7") (name "/SENSC1_2") (class "Default")
      (node (ref "J15") (pin "9") (pinfunction "9_9") (pintype "bidirectional"))
      (node (ref "J23") (pin "2") (pinfunction "2_2") (pintype "bidirectional"))
    )
    (net (code "8") (name "/SENSC2_1") (class "Default")
      (node (ref "J15") (pin "25") (pinfunction "25_25") (pintype "bidirectional"))
      (node (ref "J26") (pin "7") (pinfunction "7_7") (pintype "bidirectional"))
    )
    (net (code "9") (name "/SENSC2_2") (class "Default")
      (node (ref "J15") (pin "10") (pinfunction "10_10") (pintype "bidirectional"))
      (node (ref "J26") (pin "6") (pinfunction "6_6") (pintype "bidirectional"))
    )
    (net (code "10") (name "/SENSC3_1") (class "Default")
      (node (ref "J15") (pin "26") (pinfunction "26_26") (pintype "bidirectional"))
      (node (ref "J26") (pin "3") (pinfunction "3_3") (pintype "bidirectional"))
    )
    (net (code "11") (name "/SENSC3_2") (class "Default")
      (node (ref "J15") (pin "11") (pinfunction "11_11") (pintype "bidirectional"))
      (node (ref "J26") (pin "2") (pinfunction "2_2") (pintype "bidirectional"))
    )
    (net (code "12") (name "/SENSC4_1") (class "Default")
      (node (ref "J15") (pin "27") (pinfunction "27_27") (pintype "bidirectional"))
      (node (ref "J24") (pin "7") (pinfunction "7_7") (pintype "bidirectional"))
    )
    (net (code "13") (name "/SENSC4_2") (class "Default")
      (node (ref "J15") (pin "12") (pinfunction "12_12") (pintype "bidirectional"))
      (node (ref "J24") (pin "6") (pinfunction "6_6") (pintype "bidirectional"))
    )
    (net (code "14") (name "/SENSC5_1") (class "Default")
      (node (ref "J15") (pin "28") (pinfunction "28_28") (pintype "bidirectional"))
      (node (ref "J24") (pin "3") (pinfunction "3_3") (pintype "bidirectional"))
    )
    (net (code "15") (name "/SENSC5_2") (class "Default")
      (node (ref "J15") (pin "13") (pinfunction "13_13") (pintype "bidirectional"))
      (node (ref "J24") (pin "2") (pinfunction "2_2") (pintype "bidirectional"))
    )
    (net (code "16") (name "/SENSC6_1") (class "Default")
      (node (ref "J15") (pin "29") (pinfunction "29_29") (pintype "bidirectional"))
      (node (ref "J27") (pin "7") (pinfunction "7_7") (pintype "bidirectional"))
    )
    (net (code "17") (name "/SENSC6_2") (class "Default")
      (node (ref "J15") (pin "14") (pinfunction "14_14") (pintype "bidirectional"))
      (node (ref "J27") (pin "6") (pinfunction "6_6") (pintype "bidirectional"))
    )
    (net (code "18") (name "/SENSC7_1") (class "Default")
      (node (ref "J15") (pin "30") (pinfunction "30_30") (pintype "bidirectional"))
      (node (ref "J27") (pin "3") (pinfunction "3_3") (pintype "bidirectional"))
    )
    (net (code "19") (name "/SENSC7_2") (class "Default")
      (node (ref "J15") (pin "15") (pinfunction "15_15") (pintype "bidirectional"))
      (node (ref "J27") (pin "2") (pinfunction "2_2") (pintype "bidirectional"))
    )
    (net (code "20") (name "/TECC0+") (class "Default")
      (node (ref "J14") (pin "5") (pinfunction "5_5") (pintype "bidirectional"))
      (node (ref "J15") (pin "31") (pinfunction "31_31") (pintype "bidirectional"))
      (node (ref "J15") (pin "32") (pinfunction "32_32") (pintype "bidirectional"))
    )
    (net (code "21") (name "/TECC0-") (class "Default")
      (node (ref "J14") (pin "4") (pinfunction "4_4") (pintype "bidirectional"))
      (node (ref "J15") (pin "1") (pinfunction "1_1") (pintype "bidirectional"))
      (node (ref "J15") (pin "16") (pinfunction "16_16") (pintype "bidirectional"))
    )
    (net (code "22") (name "/TECC1+") (class "Default")
      (node (ref "J14") (pin "2") (pinfunction "2_2") (pintype "bidirectional"))
      (node (ref "J15") (pin "17") (pinfunction "17_17") (pintype "bidirectional"))
      (node (ref "J15") (pin "2") (pinfunction "2_2") (pintype "bidirectional"))
    )
    (net (code "23") (name "/TECC1-") (class "Default")
      (node (ref "J14") (pin "1") (pinfunction "1_1") (pintype "bidirectional"))
      (node (ref "J15") (pin "18") (pinfunction "18_18") (pintype "bidirectional"))
      (node (ref "J15") (pin "3") (pinfunction "3_3") (pintype "bidirectional"))
    )
    (net (code "24") (name "/TECC2+") (class "Default")
      (node (ref "J15") (pin "19") (pinfunction "19_19") (pintype "bidirectional"))
      (node (ref "J15") (pin "4") (pinfunction "4_4") (pintype "bidirectional"))
      (node (ref "J16") (pin "5") (pinfunction "5_5") (pintype "bidirectional"))
    )
    (net (code "25") (name "/TECC2-") (class "Default")
      (node (ref "J15") (pin "20") (pinfunction "20_20") (pintype "bidirectional"))
      (node (ref "J15") (pin "5") (pinfunction "5_5") (pintype "bidirectional"))
      (node (ref "J16") (pin "4") (pinfunction "4_4") (pintype "bidirectional"))
    )
    (net (code "26") (name "/TECC3+") (class "Default")
      (node (ref "J15") (pin "21") (pinfunction "21_21") (pintype "bidirectional"))
      (node (ref "J15") (pin "6") (pinfunction "6_6") (pintype "bidirectional"))
      (node (ref "J16") (pin "2") (pinfunction "2_2") (pintype "bidirectional"))
    )
    (net (code "27") (name "/TECC3-") (class "Default")
      (node (ref "J15") (pin "22") (pinfunction "22_22") (pintype "bidirectional"))
      (node (ref "J15") (pin "7") (pinfunction "7_7") (pintype "bidirectional"))
      (node (ref "J16") (pin "1") (pinfunction "1_1") (pintype "bidirectional"))
    )
    (net (code "28") (name "/Vrefc0+") (class "Default")
      (node (ref "J15") (pin "37") (pinfunction "37_37") (pintype "bidirectional"))
    )
    (net (code "29") (name "/Vrefc0-") (class "Default")
      (node (ref "J15") (pin "38") (pinfunction "38_38") (pintype "bidirectional"))
    )
    (net (code "30") (name "/Vrefc1+") (class "Default")
      (node (ref "J15") (pin "39") (pinfunction "39_39") (pintype "bidirectional"))
    )
    (net (code "31") (name "/Vrefc1-") (class "Default")
      (node (ref "J15") (pin "40") (pinfunction "40_40") (pintype "bidirectional"))
    )
    (net (code "32") (name "/Vrefc2+") (class "Default")
      (node (ref "J15") (pin "41") (pinfunction "41_41") (pintype "bidirectional"))
    )
    (net (code "33") (name "/Vrefc2-") (class "Default")
      (node (ref "J15") (pin "42") (pinfunction "42_42") (pintype "bidirectional"))
    )
    (net (code "34") (name "/Vrefc3+") (class "Default")
      (node (ref "J15") (pin "43") (pinfunction "43_43") (pintype "bidirectional"))
    )
    (net (code "35") (name "/Vrefc3-") (class "Default")
      (node (ref "J15") (pin "44") (pinfunction "44_44") (pintype "bidirectional"))
    )
    (net (code "36") (name "GND") (class "Default")
      (node (ref "C116") (pin "1") (pinfunction "1_1") (pintype "passive"))
      (node (ref "C124") (pin "2") (pinfunction "2_2") (pintype "passive"))
      (node (ref "C125") (pin "1") (pinfunction "1_1") (pintype "passive"))
      (node (ref "C132") (pin "2") (pinfunction "2_2") (pintype "passive"))
      (node (ref "C133") (pin "1") (pinfunction "1_1") (pintype "passive"))
      (node (ref "C134") (pin "1") (pinfunction "1_1") (pintype "passive"))
      (node (ref "C135") (pin "1") (pinfunction "1_1") (pintype "passive"))
      (node (ref "C142") (pin "1") (pinfunction "1_1") (pintype "passive"))
      (node (ref "C143") (pin "1") (pinfunction "1_1") (pintype "passive"))
      (node (ref "D35") (pin "2") (pinfunction "GND_2") (pintype "power_in"))
      (node (ref "IC10") (pin "1") (pinfunction "GND_1") (pintype "power_in"))
      (node (ref "IC10") (pin "4") (pinfunction "GND_4") (pintype "power_in"))
      (node (ref "IC10") (pin "7") (pinfunction "GND_7") (pintype "power_in"))
      (node (ref "IC10") (pin "8") (pinfunction "GND_8") (pintype "power_in"))
      (node (ref "IC20") (pin "2") (pinfunction "VSS_2") (pintype "power_in"))
      (node (ref "IC21") (pin "2") (pinfunction "GND_2") (pintype "power_in"))
      (node (ref "IC24") (pin "4") (pinfunction "-V_4") (pintype "power_in"))
      (node (ref "IC25") (pin "4") (pinfunction "-V_4") (pintype "power_in"))
      (node (ref "IC26") (pin "4") (pinfunction "-V_4") (pintype "power_in"))
      (node (ref "IC27") (pin "4") (pinfunction "-V_4") (pintype "power_in"))
      (node (ref "J14") (pin "3") (pinfunction "3_3") (pintype "bidirectional"))
      (node (ref "J15") (pin "36") (pinfunction "36_36") (pintype "bidirectional"))
      (node (ref "J15") (pin "45") (pinfunction "45_45") (pintype "passive"))
      (node (ref "J15") (pin "46") (pinfunction "46_46") (pintype "passive"))
      (node (ref "J16") (pin "3") (pinfunction "3_3") (pintype "bidirectional"))
      (node (ref "R188") (pin "1") (pinfunction "1_1") (pintype "passive"))
      (node (ref "R189") (pin "1") (pinfunction "1_1") (pintype "passive"))
      (node (ref "R200") (pin "1") (pinfunction "1_1") (pintype "passive"))
      (node (ref "R201") (pin "1") (pinfunction "1_1") (pintype "passive"))
      (node (ref "R208") (pin "1") (pinfunction "1_1") (pintype "passive"))
      (node (ref "R209") (pin "1") (pinfunction "1_1") (pintype "passive"))
      (node (ref "R216") (pin "1") (pinfunction "1_1") (pintype "passive"))
      (node (ref "R217") (pin "1") (pinfunction "1_1") (pintype "passive"))
      (node (ref "TP1") (pin "1") (pinfunction "1_1") (pintype "bidirectional"))
    )
    (net (code "37") (name "Net-(IC21-EN)") (class "Default")
      (node (ref "C124") (pin "1") (pinfunction "1_1") (pintype "passive"))
      (node (ref "IC21") (pin "1") (pinfunction "VIN_1") (pintype "input"))
      (node (ref "IC21") (pin "3") (pinfunction "EN_3") (pintype "input"))
      (node (ref "R45") (pin "2") (pinfunction "2_2") (pintype "passive"))
    )
    (net (code "38") (name "Net-(IC24A-+IN_A)") (class "Default")
      (node (ref "IC24") (pin "3") (pinfunction "+IN_A_3") (pintype "input"))
      (node (ref "R184") (pin "2") (pinfunction "2_2") (pintype "passive"))
    )
    (net (code "39") (name "Net-(IC24A--IN_A)") (class "Default")
      (node (ref "C136") (pin "1") (pinfunction "1_1") (pintype "passive"))
      (node (ref "IC24") (pin "2") (pinfunction "-IN_A_2") (pintype "input"))
      (node (ref "R186") (pin "2") (pinfunction "2_2") (pintype "passive"))
    )
    (net (code "40") (name "Net-(IC24A-OUT_A)") (class "Default")
      (node (ref "C136") (pin "2") (pinfunction "2_2") (pintype "passive"))
      (node (ref "IC24") (pin "1") (pinfunction "OUT_A_1") (pintype "output"))
      (node (ref "R182") (pin "1") (pinfunction "1_1") (pintype "passive"))
    )
    (net (code "41") (name "Net-(IC24B-+IN_B)") (class "Default")
      (node (ref "IC24") (pin "5") (pinfunction "+IN_B_5") (pintype "input"))
      (node (ref "R192") (pin "2") (pinfunction "2_2") (pintype "passive"))
    )
    (net (code "42") (name "Net-(IC24B--IN_B)") (class "Default")
      (node (ref "C140") (pin "1") (pinfunction "1_1") (pintype "passive"))
      (node (ref "IC24") (pin "6") (pinfunction "-IN_B_6") (pintype "input"))
      (node (ref "R198") (pin "2") (pinfunction "2_2") (pintype "passive"))
    )
    (net (code "43") (name "Net-(IC24B-OUT_B)") (class "Default")
      (node (ref "C140") (pin "2") (pinfunction "2_2") (pintype "passive"))
      (node (ref "IC24") (pin "7") (pinfunction "OUT_B_7") (pintype "output"))
      (node (ref "R190") (pin "1") (pinfunction "1_1") (pintype "passive"))
    )
    (net (code "44") (name "Net-(IC25A-+IN_A)") (class "Default")
      (node (ref "IC25") (pin "3") (pinfunction "+IN_A_3") (pintype "input"))
      (node (ref "R185") (pin "2") (pinfunction "2_2") (pintype "passive"))
    )
    (net (code "45") (name "Net-(IC25A--IN_A)") (class "Default")
      (node (ref "C137") (pin "1") (pinfunction "1_1") (pintype "passive"))
      (node (ref "IC25") (pin "2") (pinfunction "-IN_A_2") (pintype "input"))
      (node (ref "R187") (pin "2") (pinfunction "2_2") (pintype "passive"))
    )
    (net (code "46") (name "Net-(IC25A-OUT_A)") (class "Default")
      (node (ref "C137") (pin "2") (pinfunction "2_2") (pintype "passive"))
      (node (ref "IC25") (pin "1") (pinfunction "OUT_A_1") (pintype "output"))
      (node (ref "R183") (pin "1") (pinfunction "1_1") (pintype "passive"))
    )
    (net (code "47") (name "Net-(IC25B-+IN_B)") (class "Default")
      (node (ref "IC25") (pin "5") (pinfunction "+IN_B_5") (pintype "input"))
      (node (ref "R193") (pin "2") (pinfunction "2_2") (pintype "passive"))
    )
    (net (code "48") (name "Net-(IC25B--IN_B)") (class "Default")
      (node (ref "C141") (pin "1") (pinfunction "1_1") (pintype "passive"))
      (node (ref "IC25") (pin "6") (pinfunction "-IN_B_6") (pintype "input"))
      (node (ref "R199") (pin "2") (pinfunction "2_2") (pintype "passive"))
    )
    (net (code "49") (name "Net-(IC25B-OUT_B)") (class "Default")
      (node (ref "C141") (pin "2") (pinfunction "2_2") (pintype "passive"))
      (node (ref "IC25") (pin "7") (pinfunction "OUT_B_7") (pintype "output"))
      (node (ref "R191") (pin "1") (pinfunction "1_1") (pintype "passive"))
    )
    (net (code "50") (name "Net-(IC26A-+IN_A)") (class "Default")
      (node (ref "IC26") (pin "3") (pinfunction "+IN_A_3") (pintype "input"))
      (node (ref "R204") (pin "2") (pinfunction "2_2") (pintype "passive"))
    )
    (net (code "51") (name "Net-(IC26A--IN_A)") (class "Default")
      (node (ref "C149") (pin "1") (pinfunction "1_1") (pintype "passive"))
      (node (ref "IC26") (pin "2") (pinfunction "-IN_A_2") (pintype "input"))
      (node (ref "R206") (pin "2") (pinfunction "2_2") (pintype "passive"))
    )
    (net (code "52") (name "Net-(IC26A-OUT_A)") (class "Default")
      (node (ref "C149") (pin "2") (pinfunction "2_2") (pintype "passive"))
      (node (ref "IC26") (pin "1") (pinfunction "OUT_A_1") (pintype "output"))
      (node (ref "R202") (pin "1") (pinfunction "1_1") (pintype "passive"))
    )
    (net (code "53") (name "Net-(IC26B-+IN_B)") (class "Default")
      (node (ref "IC26") (pin "5") (pinfunction "+IN_B_5") (pintype "input"))
      (node (ref "R212") (pin "2") (pinfunction "2_2") (pintype "passive"))
    )
    (net (code "54") (name "Net-(IC26B--IN_B)") (class "Default")
      (node (ref "C153") (pin "1") (pinfunction "1_1") (pintype "passive"))
      (node (ref "IC26") (pin "6") (pinfunction "-IN_B_6") (pintype "input"))
      (node (ref "R214") (pin "2") (pinfunction "2_2") (pintype "passive"))
    )
    (net (code "55") (name "Net-(IC26B-OUT_B)") (class "Default")
      (node (ref "C153") (pin "2") (pinfunction "2_2") (pintype "passive"))
      (node (ref "IC26") (pin "7") (pinfunction "OUT_B_7") (pintype "output"))
      (node (ref "R210") (pin "1") (pinfunction "1_1") (pintype "passive"))
    )
    (net (code "56") (name "Net-(IC27A-+IN_A)") (class "Default")
      (node (ref "IC27") (pin "3") (pinfunction "+IN_A_3") (pintype "input"))
      (node (ref "R205") (pin "2") (pinfunction "2_2") (pintype "passive"))
    )
    (net (code "57") (name "Net-(IC27A--IN_A)") (class "Default")
      (node (ref "C150") (pin "1") (pinfunction "1_1") (pintype "passive"))
      (node (ref "IC27") (pin "2") (pinfunction "-IN_A_2") (pintype "input"))
      (node (ref "R207") (pin "2") (pinfunction "2_2") (pintype "passive"))
    )
    (net (code "58") (name "Net-(IC27A-OUT_A)") (class "Default")
      (node (ref "C150") (pin "2") (pinfunction "2_2") (pintype "passive"))
      (node (ref "IC27") (pin "1") (pinfunction "OUT_A_1") (pintype "output"))
      (node (ref "R203") (pin "1") (pinfunction "1_1") (pintype "passive"))
    )
    (net (code "59") (name "Net-(IC27B-+IN_B)") (class "Default")
      (node (ref "IC27") (pin "5") (pinfunction "+IN_B_5") (pintype "input"))
      (node (ref "R213") (pin "2") (pinfunction "2_2") (pintype "passive"))
    )
    (net (code "60") (name "Net-(IC27B--IN_B)") (class "Default")
      (node (ref "C154") (pin "1") (pinfunction "1_1") (pintype "passive"))
      (node (ref "IC27") (pin "6") (pinfunction "-IN_B_6") (pintype "input"))
      (node (ref "R215") (pin "2") (pinfunction "2_2") (pintype "passive"))
    )
    (net (code "61") (name "Net-(IC27B-OUT_B)") (class "Default")
      (node (ref "C154") (pin "2") (pinfunction "2_2") (pintype "passive"))
      (node (ref "IC27") (pin "7") (pinfunction "OUT_B_7") (pintype "output"))
      (node (ref "R211") (pin "1") (pinfunction "1_1") (pintype "passive"))
    )
    (net (code "62") (name "Net-(J23-Pad1)") (class "Default")
      (node (ref "J23") (pin "1") (pinfunction "1_1") (pintype "bidirectional"))
      (node (ref "R198") (pin "1") (pinfunction "1_1") (pintype "passive"))
      (node (ref "R200") (pin "2") (pinfunction "2_2") (pintype "passive"))
    )
    (net (code "63") (name "Net-(J23-Pad4)") (class "Default")
      (node (ref "J23") (pin "4") (pinfunction "4_4") (pintype "bidirectional"))
      (node (ref "R190") (pin "2") (pinfunction "2_2") (pintype "passive"))
    )
    (net (code "64") (name "Net-(J23-Pad5)") (class "Default")
      (node (ref "J23") (pin "5") (pinfunction "5_5") (pintype "bidirectional"))
      (node (ref "R186") (pin "1") (pinfunction "1_1") (pintype "passive"))
      (node (ref "R188") (pin "2") (pinfunction "2_2") (pintype "passive"))
    )
    (net (code "65") (name "Net-(J23-Pad8)") (class "Default")
      (node (ref "J23") (pin "8") (pinfunction "8_8") (pintype "bidirectional"))
      (node (ref "R182") (pin "2") (pinfunction "2_2") (pintype "passive"))
    )
    (net (code "66") (name "Net-(J24-Pad1)") (class "Default")
      (node (ref "J24") (pin "1") (pinfunction "1_1") (pintype "bidirectional"))
      (node (ref "R199") (pin "1") (pinfunction "1_1") (pintype "passive"))
      (node (ref "R201") (pin "2") (pinfunction "2_2") (pintype "passive"))
    )
    (net (code "67") (name "Net-(J24-Pad4)") (class "Default")
      (node (ref "J24") (pin "4") (pinfunction "4_4") (pintype "bidirectional"))
      (node (ref "R191") (pin "2") (pinfunction "2_2") (pintype "passive"))
    )
    (net (code "68") (name "Net-(J24-Pad5)") (class "Default")
      (node (ref "J24") (pin "5") (pinfunction "5_5") (pintype "bidirectional"))
      (node (ref "R187") (pin "1") (pinfunction "1_1") (pintype "passive"))
      (node (ref "R189") (pin "2") (pinfunction "2_2") (pintype "passive"))
    )
    (net (code "69") (name "Net-(J24-Pad8)") (class "Default")
      (node (ref "J24") (pin "8") (pinfunction "8_8") (pintype "bidirectional"))
      (node (ref "R183") (pin "2") (pinfunction "2_2") (pintype "passive"))
    )
    (net (code "70") (name "Net-(J26-Pad1)") (class "Default")
      (node (ref "J26") (pin "1") (pinfunction "1_1") (pintype "bidirectional"))
      (node (ref "R214") (pin "1") (pinfunction "1_1") (pintype "passive"))
      (node (ref "R216") (pin "2") (pinfunction "2_2") (pintype "passive"))
    )
    (net (code "71") (name "Net-(J26-Pad4)") (class "Default")
      (node (ref "J26") (pin "4") (pinfunction "4_4") (pintype "bidirectional"))
      (node (ref "R210") (pin "2") (pinfunction "2_2") (pintype "passive"))
    )
    (net (code "72") (name "Net-(J26-Pad5)") (class "Default")
      (node (ref "J26") (pin "5") (pinfunction "5_5") (pintype "bidirectional"))
      (node (ref "R206") (pin "1") (pinfunction "1_1") (pintype "passive"))
      (node (ref "R208") (pin "2") (pinfunction "2_2") (pintype "passive"))
    )
    (net (code "73") (name "Net-(J26-Pad8)") (class "Default")
      (node (ref "J26") (pin "8") (pinfunction "8_8") (pintype "bidirectional"))
      (node (ref "R202") (pin "2") (pinfunction "2_2") (pintype "passive"))
    )
    (net (code "74") (name "Net-(J27-Pad1)") (class "Default")
      (node (ref "J27") (pin "1") (pinfunction "1_1") (pintype "bidirectional"))
      (node (ref "R215") (pin "1") (pinfunction "1_1") (pintype "passive"))
      (node (ref "R217") (pin "2") (pinfunction "2_2") (pintype "passive"))
    )
    (net (code "75") (name "Net-(J27-Pad4)") (class "Default")
      (node (ref "J27") (pin "4") (pinfunction "4_4") (pintype "bidirectional"))
      (node (ref "R211") (pin "2") (pinfunction "2_2") (pintype "passive"))
    )
    (net (code "76") (name "Net-(J27-Pad5)") (class "Default")
      (node (ref "J27") (pin "5") (pinfunction "5_5") (pintype "bidirectional"))
      (node (ref "R207") (pin "1") (pinfunction "1_1") (pintype "passive"))
      (node (ref "R209") (pin "2") (pinfunction "2_2") (pintype "passive"))
    )
    (net (code "77") (name "Net-(J27-Pad8)") (class "Default")
      (node (ref "J27") (pin "8") (pinfunction "8_8") (pintype "bidirectional"))
      (node (ref "R203") (pin "2") (pinfunction "2_2") (pintype "passive"))
    )
    (net (code "78") (name "P3V3_AFEC") (class "Default")
      (node (ref "C116") (pin "2") (pinfunction "2_2") (pintype "passive"))
      (node (ref "C125") (pin "2") (pinfunction "2_2") (pintype "passive"))
      (node (ref "D35") (pin "5") (pinfunction "VBUS_5") (pintype "power_in"))
      (node (ref "IC20") (pin "4") (pinfunction "VCC_4") (pintype "power_in"))
      (node (ref "IC21") (pin "5") (pinfunction "VOUT_5") (pintype "power_in"))
      (node (ref "TP14") (pin "1") (pinfunction "1_1") (pintype "bidirectional"))
    )
    (net (code "79") (name "P5V0_AFEC") (class "Default")
      (node (ref "C132") (pin "1") (pinfunction "1_1") (pintype "passive"))
      (node (ref "C134") (pin "2") (pinfunction "2_2") (pintype "passive"))
      (node (ref "C135") (pin "2") (pinfunction "2_2") (pintype "passive"))
      (node (ref "C142") (pin "2") (pinfunction "2_2") (pintype "passive"))
      (node (ref "C143") (pin "2") (pinfunction "2_2") (pintype "passive"))
      (node (ref "IC10") (pin "2") (pinfunction "VIN_2") (pintype "input"))
      (node (ref "IC10") (pin "3") (pinfunction "EN_3") (pintype "input"))
      (node (ref "IC24") (pin "8") (pinfunction "+V_8") (pintype "power_in"))
      (node (ref "IC25") (pin "8") (pinfunction "+V_8") (pintype "power_in"))
      (node (ref "IC26") (pin "8") (pinfunction "+V_8") (pintype "power_in"))
      (node (ref "IC27") (pin "8") (pinfunction "+V_8") (pintype "power_in"))
      (node (ref "J15") (pin "33") (pinfunction "33_33") (pintype "bidirectional"))
      (node (ref "R45") (pin "1") (pinfunction "1_1") (pintype "passive"))
    )
    (net (code "80") (name "unconnected-(B1-Pad1)") (class "Default")
      (node (ref "B1") (pin "1") (pinfunction "1_1") (pintype "bidirectional"))
    )
    (net (code "81") (name "unconnected-(B2-Pad1)") (class "Default")
      (node (ref "B2") (pin "1") (pinfunction "1_1") (pintype "bidirectional"))
    )
    (net (code "82") (name "unconnected-(B3-Pad1)") (class "Default")
      (node (ref "B3") (pin "1") (pinfunction "1_1") (pintype "bidirectional"))
    )
    (net (code "83") (name "unconnected-(B4-Pad1)") (class "Default")
      (node (ref "B4") (pin "1") (pinfunction "1_1") (pintype "bidirectional"))
    )
    (net (code "84") (name "unconnected-(D35-I{slash}O1-Pad1)") (class "Default")
      (node (ref "D35") (pin "1") (pinfunction "I/O1_1") (pintype "bidirectional+no_connect"))
    )
    (net (code "85") (name "unconnected-(D35-I{slash}O2-Pad3)") (class "Default")
      (node (ref "D35") (pin "3") (pinfunction "I/O2_3") (pintype "bidirectional+no_connect"))
    )
    (net (code "86") (name "unconnected-(IC10-NC-Pad5)") (class "Default")
      (node (ref "IC10") (pin "5") (pinfunction "NC_5") (pintype "passive"))
    )
    (net (code "87") (name "unconnected-(IC20-NC-Pad5)") (class "Default")
      (node (ref "IC20") (pin "5") (pinfunction "NC_5") (pintype "passive+no_connect"))
    )
    (net (code "88") (name "unconnected-(IC21-NC-Pad4)") (class "Default")
      (node (ref "IC21") (pin "4") (pinfunction "NC_4") (pintype "passive+no_connect"))
    )
  )
)
